# SheetMSP.net
KiCad netlist of a schematic drawn in Altium Designer
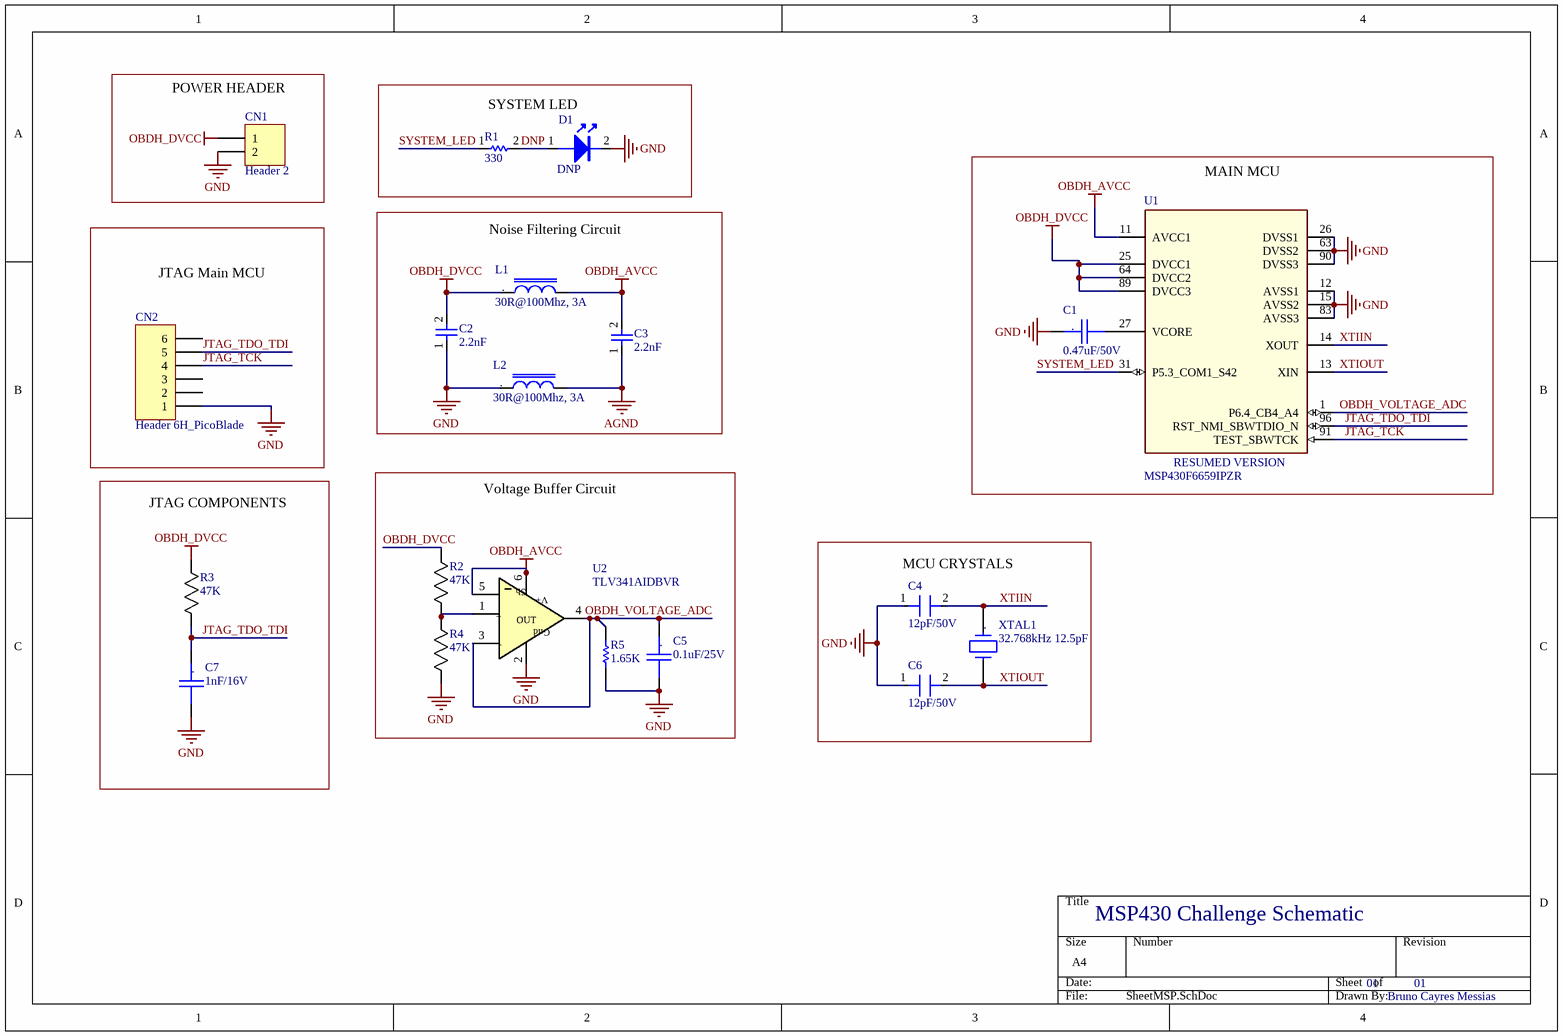
[diagram p0: SheetMSP.SchDoc]

(export (version "E")
  (design (tool "Eeschema 10.0.6"))
  (components
    (comp (ref "C1")
      (value "0.47uF/50V")
      (footprint "C0805_MD")
      (description "CAP CER 0.47UF 50V 10% X7R 0805")
      (fields (field (name "PARTNUMBER") "C0805C474K5RACTU"))
      (libsource (lib "MPS430_Task") (part "Cap_Cer_X7R_0.47uF_50V_0805"))
    )
    (comp (ref "C2")
      (value "2.2nF")
      (footprint "GRM155R71C222KA01D")
      (description "Imported")
      (fields
        (field (name "MANUFACTURER_PART_NUMBER") "GRM155R71C222KA01D")
        (field (name "MANUFACTURER") "Murata")
      )
      (libsource (lib "MPS430_Task") (part "Cap 2.2nF/16V_0402"))
    )
    (comp (ref "C3")
      (value "2.2nF")
      (footprint "GRM155R71C222KA01D")
      (description "Imported")
      (fields
        (field (name "MANUFACTURER_PART_NUMBER") "GRM155R71C222KA01D")
        (field (name "MANUFACTURER") "Murata")
      )
      (libsource (lib "MPS430_Task") (part "Cap 2.2nF/16V_0402"))
    )
    (comp (ref "C4")
      (value "12pF/50V")
      (footprint "Cap_12pf")
      (fields
        (field (name "MANUFACTURER") "KEMET")
        (field (name "MANUFACTURER PART NUMBER") "CBR04C120F5GAC")
        (field (name "TOLERANCE") "1%")
      )
      (libsource (lib "MPS430_Task") (part "CBR04C120F5GAC"))
    )
    (comp (ref "C5")
      (value "0.1uF/25V")
      (footprint "C0805_MD")
      (description "CAP CER 0.1UF 25V 10% X7R 0805")
      (fields (field (name "PARTNUMBER") "CC0805KRX7R8BB104"))
      (libsource (lib "MPS430_Task") (part "Cap_Cer_X7R_0.1uF_25V_0805"))
    )
    (comp (ref "C6")
      (value "12pF/50V")
      (footprint "Cap_12pf")
      (fields
        (field (name "MANUFACTURER") "KEMET")
        (field (name "MANUFACTURER PART NUMBER") "CBR04C120F5GAC")
        (field (name "TOLERANCE") "1%")
      )
      (libsource (lib "MPS430_Task") (part "CBR04C120F5GAC"))
    )
    (comp (ref "C7")
      (value "1nF/16V")
      (footprint "C0603_MD")
      (description "CAP CER 1nF 16V 0603 5%")
      (fields (field (name "PARTNUMBER") "C0603X102J4RECAUTO"))
      (libsource (lib "MPS430_Task") (part "Cap_Cer_X7R_1nF_16V_0603"))
    )
    (comp (ref "CN1")
      (value "Header 2")
      (footprint "HEADER 2M 2.54mm 180 GRAUS")
      (description "Header, 2-Pin")
      (fields (field (name "PARTNUMBER") "826646-2") (field (name "PUBLISHER") "Altium Limited"))
      (libsource (lib "MPS430_Task") (part "Header 2"))
    )
    (comp (ref "CN2")
      (value "Header 6H_PicoBlade")
      (footprint "PICO BLADE 0532610671")
      (description "Header, 6-Pin, Right Angle")
      (fields (field (name "PARTNUMBER") "53398-0671") (field (name "PUBLISHER") "Altium Limited"))
      (libsource (lib "MPS430_Task") (part "Header 6H_PicoBlade"))
    )
    (comp (ref "D1")
      (value "DNP")
      (footprint "L0805 GREEN")
      (description "SMD Green LED")
      (fields (field (name "PARTNUMBER") "LTST-C171GKT"))
      (libsource (lib "MPS430_Task") (part "LED/G_0805"))
    )
    (comp (ref "L1")
      (value "30R@100Mhz, 3A")
      (footprint "L0805")
      (description "Ferrite Bead 30 OHM 3A 100MHz")
      (fields (field (name "PARTNUMBER") "BLM21PG300SN1D"))
      (libsource (lib "MPS430_Task") (part "FB_30R_3A_100MHz_0805"))
    )
    (comp (ref "L2")
      (value "30R@100Mhz, 3A")
      (footprint "L0805")
      (description "Ferrite Bead 30 OHM 3A 100MHz")
      (fields (field (name "PARTNUMBER") "BLM21PG300SN1D"))
      (libsource (lib "MPS430_Task") (part "FB_30R_3A_100MHz_0805"))
    )
    (comp (ref "R1")
      (value "330")
      (footprint "R0603_MD")
      (fields
        (field (name "MANUFACTURER") "Vishay")
        (field (name "MANUFACTURER PART NUMBER") "CRCW0603330RFKEAHP")
        (field (name "TOLERANCE") "1%")
      )
      (libsource (lib "MPS430_Task") (part "Resistor 330"))
    )
    (comp (ref "R2")
      (value "47K")
      (footprint "R0805_MD")
      (description "Imported")
      (fields
        (field (name "MANUFACTURER_PART_NUMBER") "ERA-6AEB473V")
        (field (name "MANUFACTURER") "Panasonic ECG")
      )
      (libsource (lib "MPS430_Task") (part "Resistor 47 Kohms"))
    )
    (comp (ref "R3")
      (value "47K")
      (footprint "R0805_MD")
      (description "Imported")
      (fields
        (field (name "MANUFACTURER_PART_NUMBER") "ERA-6AEB473V")
        (field (name "MANUFACTURER") "Panasonic ECG")
      )
      (libsource (lib "MPS430_Task") (part "Resistor 47 Kohms"))
    )
    (comp (ref "R4")
      (value "47K")
      (footprint "R0805_MD")
      (description "Imported")
      (fields
        (field (name "MANUFACTURER_PART_NUMBER") "ERA-6AEB473V")
        (field (name "MANUFACTURER") "Panasonic ECG")
      )
      (libsource (lib "MPS430_Task") (part "Resistor 47 Kohms"))
    )
    (comp (ref "R5")
      (value "1.65K")
      (footprint "R0805_MD")
      (description "RES 1.65K OHM 1/10W 0.1% 0805")
      (fields (field (name "PARTNUMBER") "PCF0805R-1K65BT1"))
      (libsource (lib "MPS430_Task") (part "R1.65K_1%_1/10W_0805"))
    )
    (comp (ref "U1")
      (value "MSP430F6659IPZR")
      (footprint "PZ0100A_N")
      (fields (field (name "MANUFACTURER") "Texas Instruments"))
      (libsource (lib "MPS430_Task") (part "MSP430F6659IPZR"))
    )
    (comp (ref "U2")
      (value "TLV341AIDBVR")
      (footprint "TLV341AIDBVR")
      (libsource (lib "MPS430_Task") (part "TLV341AIDBVR"))
    )
    (comp (ref "XTAL1")
      (value "32.768kHz 12.5pF")
      (footprint "ABS06 0805")
      (description "32.768kHz ±20ppm Crystal 12.5pF 70 kOhm -40°C ~ 125°C")
      (fields (field (name "PARTNUMBER") "ECS-.327-12.5-34S-TR"))
      (libsource (lib "MPS430_Task") (part "Xtal_32.768kHz_12pF_2_SMD"))
    )
  )
  (nets
    (net (code "1") (name "/DNP") (class "Default")
      (node (ref "D1") (pin "1") (pinfunction "1_1") (pintype "passive"))
      (node (ref "R1") (pin "2") (pinfunction "2_2") (pintype "passive"))
    )
    (net (code "2") (name "/JTAG_TCK") (class "Default")
      (node (ref "CN2") (pin "4") (pinfunction "4_4") (pintype "passive"))
      (node (ref "U1") (pin "91") (pinfunction "TEST_SBWTCK_91") (pintype "input"))
    )
    (net (code "3") (name "/JTAG_TDO_TDI") (class "Default")
      (node (ref "C7") (pin "1") (pinfunction "1_1") (pintype "passive"))
      (node (ref "CN2") (pin "5") (pinfunction "5_5") (pintype "passive"))
      (node (ref "R3") (pin "2") (pinfunction "2_2") (pintype "passive"))
      (node (ref "U1") (pin "96") (pinfunction "RST_NMI_SBWTDIO_N_96") (pintype "bidirectional"))
    )
    (net (code "4") (name "/OBDH_VOLTAGE_ADC") (class "Default")
      (node (ref "C5") (pin "1") (pinfunction "1_1") (pintype "passive"))
      (node (ref "R5") (pin "2") (pinfunction "2_2") (pintype "passive"))
      (node (ref "U1") (pin "1") (pinfunction "P6.4_CB4_A4_1") (pintype "bidirectional"))
      (node (ref "U2") (pin "3") (pinfunction "-IN_3") (pintype "passive"))
      (node (ref "U2") (pin "4") (pinfunction "OUT_4") (pintype "passive"))
    )
    (net (code "5") (name "/SYSTEM_LED") (class "Default")
      (node (ref "R1") (pin "1") (pinfunction "1_1") (pintype "passive"))
      (node (ref "U1") (pin "31") (pinfunction "P5.3_COM1_S42_31") (pintype "bidirectional"))
    )
    (net (code "6") (name "/XTIIN") (class "Default")
      (node (ref "C4") (pin "2") (pinfunction "1_2") (pintype "passive"))
      (node (ref "U1") (pin "14") (pinfunction "XOUT_14") (pintype "passive"))
      (node (ref "XTAL1") (pin "1") (pinfunction "1_1") (pintype "passive"))
    )
    (net (code "7") (name "/XTIOUT") (class "Default")
      (node (ref "C6") (pin "2") (pinfunction "1_2") (pintype "passive"))
      (node (ref "U1") (pin "13") (pinfunction "XIN_13") (pintype "passive"))
      (node (ref "XTAL1") (pin "2") (pinfunction "2_2") (pintype "passive"))
    )
    (net (code "8") (name "AGND") (class "Default")
      (node (ref "C3") (pin "1") (pinfunction "1_1") (pintype "passive"))
      (node (ref "L2") (pin "2") (pinfunction "2_2") (pintype "passive"))
    )
    (net (code "9") (name "GND") (class "Default")
      (node (ref "C1") (pin "1") (pinfunction "1_1") (pintype "passive"))
      (node (ref "C2") (pin "1") (pinfunction "1_1") (pintype "passive"))
      (node (ref "C4") (pin "1") (pinfunction "0_1") (pintype "passive"))
      (node (ref "C5") (pin "2") (pinfunction "2_2") (pintype "passive"))
      (node (ref "C6") (pin "1") (pinfunction "0_1") (pintype "passive"))
      (node (ref "C7") (pin "2") (pinfunction "2_2") (pintype "passive"))
      (node (ref "CN1") (pin "2") (pinfunction "2_2") (pintype "passive"))
      (node (ref "CN2") (pin "1") (pinfunction "1_1") (pintype "passive"))
      (node (ref "D1") (pin "2") (pinfunction "2_2") (pintype "passive"))
      (node (ref "L2") (pin "1") (pinfunction "1_1") (pintype "passive"))
      (node (ref "R4") (pin "2") (pinfunction "2_2") (pintype "passive"))
      (node (ref "R5") (pin "1") (pinfunction "1_1") (pintype "passive"))
      (node (ref "U1") (pin "12") (pinfunction "AVSS1_12") (pintype "power_in"))
      (node (ref "U1") (pin "15") (pinfunction "AVSS2_15") (pintype "power_in"))
      (node (ref "U1") (pin "26") (pinfunction "DVSS1_26") (pintype "passive"))
      (node (ref "U1") (pin "63") (pinfunction "DVSS2_63") (pintype "power_in"))
      (node (ref "U1") (pin "83") (pinfunction "AVSS3_83") (pintype "power_in"))
      (node (ref "U1") (pin "90") (pinfunction "DVSS3_90") (pintype "passive"))
      (node (ref "U2") (pin "2") (pinfunction "Gnd_2") (pintype "passive"))
    )
    (net (code "10") (name "Net-(U1-VCORE)") (class "Default")
      (node (ref "C1") (pin "2") (pinfunction "2_2") (pintype "passive"))
      (node (ref "U1") (pin "27") (pinfunction "VCORE_27") (pintype "power_in"))
    )
    (net (code "11") (name "Net-(U2-+IN)") (class "Default")
      (node (ref "R2") (pin "2") (pinfunction "2_2") (pintype "passive"))
      (node (ref "R4") (pin "1") (pinfunction "1_1") (pintype "passive"))
      (node (ref "U2") (pin "1") (pinfunction "+IN_1") (pintype "passive"))
    )
    (net (code "12") (name "OBDH_AVCC") (class "Default")
      (node (ref "C3") (pin "2") (pinfunction "2_2") (pintype "passive"))
      (node (ref "L1") (pin "2") (pinfunction "2_2") (pintype "passive"))
      (node (ref "U1") (pin "11") (pinfunction "AVCC1_11") (pintype "power_in"))
      (node (ref "U2") (pin "5") (pinfunction "EN_5") (pintype "passive"))
      (node (ref "U2") (pin "6") (pinfunction "V+_6") (pintype "passive"))
    )
    (net (code "13") (name "OBDH_DVCC") (class "Default")
      (node (ref "C2") (pin "2") (pinfunction "2_2") (pintype "passive"))
      (node (ref "CN1") (pin "1") (pinfunction "1_1") (pintype "passive"))
      (node (ref "L1") (pin "1") (pinfunction "1_1") (pintype "passive"))
      (node (ref "R2") (pin "1") (pinfunction "1_1") (pintype "passive"))
      (node (ref "R3") (pin "1") (pinfunction "1_1") (pintype "passive"))
      (node (ref "U1") (pin "25") (pinfunction "DVCC1_25") (pintype "power_in"))
      (node (ref "U1") (pin "64") (pinfunction "DVCC2_64") (pintype "power_in"))
      (node (ref "U1") (pin "89") (pinfunction "DVCC3_89") (pintype "power_in"))
    )
    (net (code "14") (name "unconnected-(CN2-Pad2)") (class "Default")
      (node (ref "CN2") (pin "2") (pinfunction "2_2") (pintype "passive"))
    )
    (net (code "15") (name "unconnected-(CN2-Pad3)") (class "Default")
      (node (ref "CN2") (pin "3") (pinfunction "3_3") (pintype "passive"))
    )
    (net (code "16") (name "unconnected-(CN2-Pad6)") (class "Default")
      (node (ref "CN2") (pin "6") (pinfunction "6_6") (pintype "passive"))
    )
  )
)
